# Microcontroller.net
KiCad netlist of a schematic drawn in Altium Designer
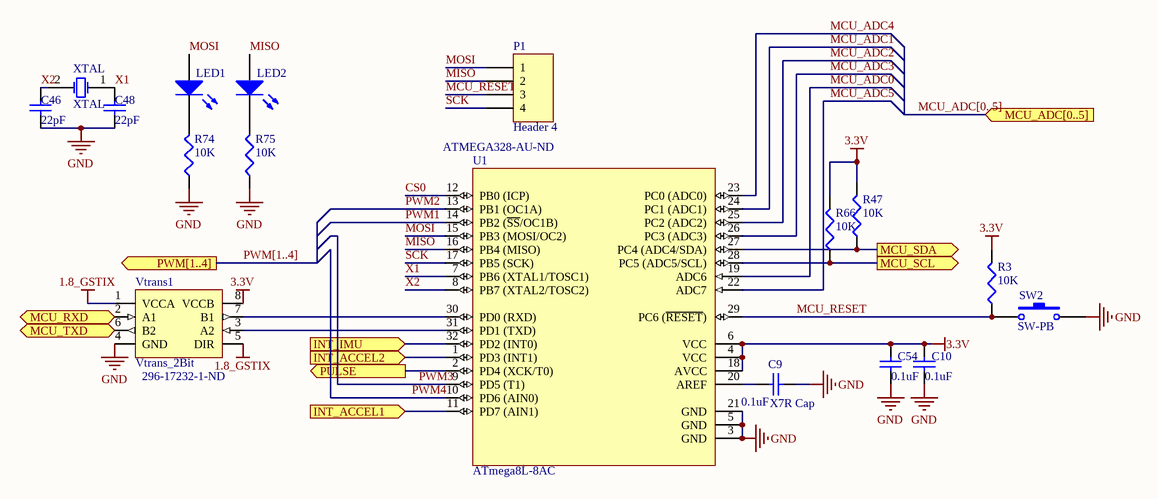
[diagram p0: Microcontroller.SchDoc]

(export (version "E")
  (design (tool "Eeschema 10.0.6"))
  (components
    (comp (ref "C9")
      (value "X7R Cap")
      (footprint "0603_CAP")
      (description "Capacitor")
      (fields (field (name "ALTIUM_VALUE") "0.1uF") (field (name "PUBLISHER") "Altium Limited"))
      (libsource (lib "Miscellaneous Devices") (part "Cap"))
    )
    (comp (ref "C10")
      (value "0.1uF")
      (footprint "0603_CAP")
      (description "Capacitor")
      (fields (field (name "Comment") "X7R Cap") (field (name "PUBLISHER") "Altium Limited"))
      (libsource (lib "Miscellaneous Devices") (part "Cap"))
    )
    (comp (ref "C46")
      (value "22pF")
      (footprint "0603_CAP")
      (description "Capacitor")
      (fields (field (name "Comment") "X7R Cap") (field (name "PUBLISHER") "Altium Limited"))
      (libsource (lib "Miscellaneous Devices") (part "Cap"))
    )
    (comp (ref "C48")
      (value "22pF")
      (footprint "0603_CAP")
      (description "Capacitor")
      (fields (field (name "Comment") "X7R Cap") (field (name "PUBLISHER") "Altium Limited"))
      (libsource (lib "Miscellaneous Devices") (part "Cap"))
    )
    (comp (ref "C54")
      (value "0.1uF")
      (footprint "0603_CAP")
      (description "Capacitor")
      (fields (field (name "Comment") "X7R Cap") (field (name "PUBLISHER") "Altium Limited"))
      (libsource (lib "Miscellaneous Devices") (part "Cap"))
    )
    (comp (ref "LED1")
      (value "LED0")
      (footprint "0603_RES")
      (description "Typical INFRARED GaAs LED")
      (fields (field (name "PUBLISHER") "Altium Limited"))
      (libsource (lib "Miscellaneous Devices") (part "LED0"))
    )
    (comp (ref "LED2")
      (value "LED0")
      (footprint "0603_RES")
      (description "Typical INFRARED GaAs LED")
      (fields (field (name "PUBLISHER") "Altium Limited"))
      (libsource (lib "Miscellaneous Devices") (part "LED0"))
    )
    (comp (ref "P1")
      (value "Header 4")
      (footprint "PRG_HEADER")
      (description "Header, 4-Pin")
      (fields (field (name "PUBLISHER") "Altium Limited"))
      (libsource (lib "Miscellaneous Connectors") (part "Header 4"))
    )
    (comp (ref "R3")
      (value "10K")
      (footprint "0603_RES")
      (description "Resistor")
      (fields (field (name "Comment") "Rpull") (field (name "PUBLISHER") "Altium Limited"))
      (libsource (lib "Miscellaneous Devices") (part "Res3"))
    )
    (comp (ref "R47")
      (value "10K")
      (footprint "0603_RES")
      (description "Resistor")
      (fields (field (name "Comment") "Rpull") (field (name "PUBLISHER") "Altium Limited"))
      (libsource (lib "Miscellaneous Devices") (part "Res3"))
    )
    (comp (ref "R66")
      (value "10K")
      (footprint "0603_RES")
      (description "Resistor")
      (fields (field (name "Comment") "Rpull") (field (name "PUBLISHER") "Altium Limited"))
      (libsource (lib "Miscellaneous Devices") (part "Res3"))
    )
    (comp (ref "R74")
      (value "10K")
      (footprint "0603_RES")
      (description "Resistor")
      (fields (field (name "Comment") "Rpull") (field (name "PUBLISHER") "Altium Limited"))
      (libsource (lib "Miscellaneous Devices") (part "Res3"))
    )
    (comp (ref "R75")
      (value "10K")
      (footprint "0603_RES")
      (description "Resistor")
      (fields (field (name "Comment") "Rpull") (field (name "PUBLISHER") "Altium Limited"))
      (libsource (lib "Miscellaneous Devices") (part "Res3"))
    )
    (comp (ref "SW2")
      (value "SW-PB")
      (footprint "SM_SW")
      (description "Switch")
      (fields
        (field (name "MANUFACTURER") "C&K Components")
        (field (name "MANUFACTURER PART NUMBER") "PTS525SK08SMTR LFS")
        (field (name "PUBLISHER") "Altium Limited")
      )
      (libsource (lib "Miscellaneous Devices") (part "SW-PB"))
    )
    (comp (ref "U1")
      (value "ATmega8L-8AC")
      (footprint "32A_N")
      (description "8-Bit AVR Microcontroller with 8K Bytes of In-System Programmable Flash Memory")
      (fields
        (field (name "SUPPLIER PART NUMBER 1") "ATMEGA328-AU-ND")
        (field (name "MANUFACTURER") "Atmel")
        (field (name "MANUFACTURER PART NUMBER") "ATMEGA328-AU")
        (field (name "PUBLISHER") "Altium Limited")
      )
      (libsource (lib "Atmel Microcontroller 8-Bit AVR") (part "ATmega8L-8AC"))
    )
    (comp (ref "Vtrans1")
      (value "Vtrans_2Bit")
      (footprint "TSOP65P400X130-8N")
      (description "296-17232-1-ND")
      (fields
        (field (name "SUPPLIER PART NUMBER 1") "296-17232-1-ND")
        (field (name "MANUFACTURER") "Texas Instruments")
        (field (name "MANUFACTURER PART NUMBER") "SN74AVC2T45DCTR")
      )
      (libsource (lib "Components") (part "Vtrans_2Bit"))
    )
    (comp (ref "XTAL")
      (value "XTAL")
      (footprint "XTAL 16Mhz")
      (description "Crystal Oscillator")
      (fields (field (name "PUBLISHER") "Altium Limited"))
      (libsource (lib "Miscellaneous Devices") (part "XTAL"))
    )
  )
  (nets
    (net (code "1") (name "/CS0") (class "Default")
      (node (ref "U1") (pin "12") (pinfunction "PB0_(ICP)_12") (pintype "bidirectional"))
    )
    (net (code "2") (name "/INT_ACCEL1") (class "Default")
      (node (ref "U1") (pin "11") (pinfunction "PD7_(AIN1)_11") (pintype "bidirectional"))
    )
    (net (code "3") (name "/INT_ACCEL2") (class "Default")
      (node (ref "U1") (pin "1") (pinfunction "PD3_(INT1)_1") (pintype "bidirectional"))
    )
    (net (code "4") (name "/INT_IMU") (class "Default")
      (node (ref "U1") (pin "32") (pinfunction "PD2_(INT0)_32") (pintype "bidirectional"))
    )
    (net (code "5") (name "/MCU_ADC0") (class "Default")
      (node (ref "U1") (pin "19") (pinfunction "ADC6_19") (pintype "input"))
    )
    (net (code "6") (name "/MCU_ADC1") (class "Default")
      (node (ref "U1") (pin "24") (pinfunction "PC1_(ADC1)_24") (pintype "bidirectional"))
    )
    (net (code "7") (name "/MCU_ADC2") (class "Default")
      (node (ref "U1") (pin "25") (pinfunction "PC2_(ADC2)_25") (pintype "bidirectional"))
    )
    (net (code "8") (name "/MCU_ADC3") (class "Default")
      (node (ref "U1") (pin "26") (pinfunction "PC3_(ADC3)_26") (pintype "bidirectional"))
    )
    (net (code "9") (name "/MCU_ADC4") (class "Default")
      (node (ref "U1") (pin "23") (pinfunction "PC0_(ADC0)_23") (pintype "bidirectional"))
    )
    (net (code "10") (name "/MCU_ADC5") (class "Default")
      (node (ref "U1") (pin "22") (pinfunction "ADC7_22") (pintype "input"))
    )
    (net (code "12") (name "/MCU_RESET") (class "Default")
      (node (ref "P1") (pin "3") (pinfunction "3_3") (pintype "passive"))
      (node (ref "R3") (pin "1") (pinfunction "1_1") (pintype "passive"))
      (node (ref "SW2") (pin "1") (pinfunction "1_1") (pintype "passive"))
      (node (ref "U1") (pin "29") (pinfunction "PC6_(~{RESET})_29") (pintype "bidirectional"))
    )
    (net (code "13") (name "/MCU_RXD") (class "Default")
      (node (ref "Vtrans1") (pin "2") (pinfunction "A1_2") (pintype "input"))
    )
    (net (code "14") (name "/MCU_SCL") (class "Default")
      (node (ref "R66") (pin "1") (pinfunction "1_1") (pintype "passive"))
      (node (ref "U1") (pin "28") (pinfunction "PC5_(ADC5/SCL)_28") (pintype "bidirectional"))
    )
    (net (code "15") (name "/MCU_SDA") (class "Default")
      (node (ref "R47") (pin "1") (pinfunction "1_1") (pintype "passive"))
      (node (ref "U1") (pin "27") (pinfunction "PC4_(ADC4/SDA)_27") (pintype "bidirectional"))
    )
    (net (code "16") (name "/MCU_TXD") (class "Default")
      (node (ref "Vtrans1") (pin "6") (pinfunction "B2_6") (pintype "output"))
    )
    (net (code "17") (name "/MISO") (class "Default")
      (node (ref "LED2") (pin "1") (pinfunction "A_1") (pintype "passive"))
      (node (ref "P1") (pin "2") (pinfunction "2_2") (pintype "passive"))
      (node (ref "U1") (pin "16") (pinfunction "PB4_(MISO)_16") (pintype "bidirectional"))
    )
    (net (code "18") (name "/MOSI") (class "Default")
      (node (ref "LED1") (pin "1") (pinfunction "A_1") (pintype "passive"))
      (node (ref "P1") (pin "1") (pinfunction "1_1") (pintype "passive"))
      (node (ref "U1") (pin "15") (pinfunction "PB3_(MOSI/OC2)_15") (pintype "bidirectional"))
    )
    (net (code "19") (name "/PULSE") (class "Default")
      (node (ref "U1") (pin "2") (pinfunction "PD4_(XCK/T0)_2") (pintype "bidirectional"))
    )
    (net (code "20") (name "/PWM1") (class "Default")
      (node (ref "U1") (pin "14") (pinfunction "PB2_(~{SS}/OC1B)_14") (pintype "bidirectional"))
    )
    (net (code "21") (name "/PWM2") (class "Default")
      (node (ref "U1") (pin "13") (pinfunction "PB1_(OC1A)_13") (pintype "bidirectional"))
    )
    (net (code "22") (name "/PWM3") (class "Default")
      (node (ref "U1") (pin "9") (pinfunction "PD5_(T1)_9") (pintype "bidirectional"))
    )
    (net (code "23") (name "/PWM4") (class "Default")
      (node (ref "U1") (pin "10") (pinfunction "PD6_(AIN0)_10") (pintype "bidirectional"))
    )
    (net (code "25") (name "/SCK") (class "Default")
      (node (ref "P1") (pin "4") (pinfunction "4_4") (pintype "passive"))
      (node (ref "U1") (pin "17") (pinfunction "PB5_(SCK)_17") (pintype "bidirectional"))
    )
    (net (code "26") (name "/X1") (class "Default")
      (node (ref "C48") (pin "1") (pinfunction "1_1") (pintype "passive"))
      (node (ref "U1") (pin "7") (pinfunction "PB6_(XTAL1/TOSC1)_7") (pintype "bidirectional"))
      (node (ref "XTAL") (pin "1") (pinfunction "OSC1_1") (pintype "passive"))
    )
    (net (code "27") (name "/X2") (class "Default")
      (node (ref "C46") (pin "1") (pinfunction "1_1") (pintype "passive"))
      (node (ref "U1") (pin "8") (pinfunction "PB7_(XTAL2/TOSC2)_8") (pintype "bidirectional"))
      (node (ref "XTAL") (pin "2") (pinfunction "OSC2_2") (pintype "passive"))
    )
    (net (code "28") (name "1.8_GSTIX") (class "Default")
      (node (ref "Vtrans1") (pin "1") (pinfunction "VCCA_1") (pintype "passive"))
      (node (ref "Vtrans1") (pin "5") (pinfunction "DIR_5") (pintype "passive"))
    )
    (net (code "29") (name "3.3V") (class "Default")
      (node (ref "C10") (pin "1") (pinfunction "1_1") (pintype "passive"))
      (node (ref "C54") (pin "1") (pinfunction "1_1") (pintype "passive"))
      (node (ref "R3") (pin "2") (pinfunction "2_2") (pintype "passive"))
      (node (ref "R47") (pin "2") (pinfunction "2_2") (pintype "passive"))
      (node (ref "R66") (pin "2") (pinfunction "2_2") (pintype "passive"))
      (node (ref "U1") (pin "18") (pinfunction "AVCC_18") (pintype "power_in"))
      (node (ref "U1") (pin "4") (pinfunction "VCC_4") (pintype "power_in"))
      (node (ref "U1") (pin "6") (pinfunction "VCC_6") (pintype "power_in"))
      (node (ref "Vtrans1") (pin "8") (pinfunction "VCCB_8") (pintype "passive"))
    )
    (net (code "30") (name "GND") (class "Default")
      (node (ref "C10") (pin "2") (pinfunction "2_2") (pintype "passive"))
      (node (ref "C46") (pin "2") (pinfunction "2_2") (pintype "passive"))
      (node (ref "C48") (pin "2") (pinfunction "2_2") (pintype "passive"))
      (node (ref "C54") (pin "2") (pinfunction "2_2") (pintype "passive"))
      (node (ref "C9") (pin "1") (pinfunction "1_1") (pintype "passive"))
      (node (ref "R74") (pin "1") (pinfunction "1_1") (pintype "passive"))
      (node (ref "R75") (pin "1") (pinfunction "1_1") (pintype "passive"))
      (node (ref "SW2") (pin "2") (pinfunction "2_2") (pintype "passive"))
      (node (ref "U1") (pin "21") (pinfunction "GND_21") (pintype "power_in"))
      (node (ref "U1") (pin "3") (pinfunction "GND_3") (pintype "power_in"))
      (node (ref "U1") (pin "5") (pinfunction "GND_5") (pintype "power_in"))
      (node (ref "Vtrans1") (pin "4") (pinfunction "GND_4") (pintype "passive"))
    )
    (net (code "31") (name "Net-(LED1-K)") (class "Default")
      (node (ref "LED1") (pin "2") (pinfunction "K_2") (pintype "passive"))
      (node (ref "R74") (pin "2") (pinfunction "2_2") (pintype "passive"))
    )
    (net (code "32") (name "Net-(LED2-K)") (class "Default")
      (node (ref "LED2") (pin "2") (pinfunction "K_2") (pintype "passive"))
      (node (ref "R75") (pin "2") (pinfunction "2_2") (pintype "passive"))
    )
    (net (code "33") (name "Net-(U1-AREF)") (class "Default")
      (node (ref "C9") (pin "2") (pinfunction "2_2") (pintype "passive"))
      (node (ref "U1") (pin "20") (pinfunction "AREF_20") (pintype "passive"))
    )
    (net (code "34") (name "Net-(U1-PD0_(RXD))") (class "Default")
      (node (ref "U1") (pin "30") (pinfunction "PD0_(RXD)_30") (pintype "bidirectional"))
      (node (ref "Vtrans1") (pin "7") (pinfunction "B1_7") (pintype "output"))
    )
    (net (code "35") (name "Net-(U1-PD1_(TXD))") (class "Default")
      (node (ref "U1") (pin "31") (pinfunction "PD1_(TXD)_31") (pintype "bidirectional"))
      (node (ref "Vtrans1") (pin "3") (pinfunction "A2_3") (pintype "input"))
    )
  )
)
